# power_supply.net
KiCad netlist of a schematic drawn in Altium Designer
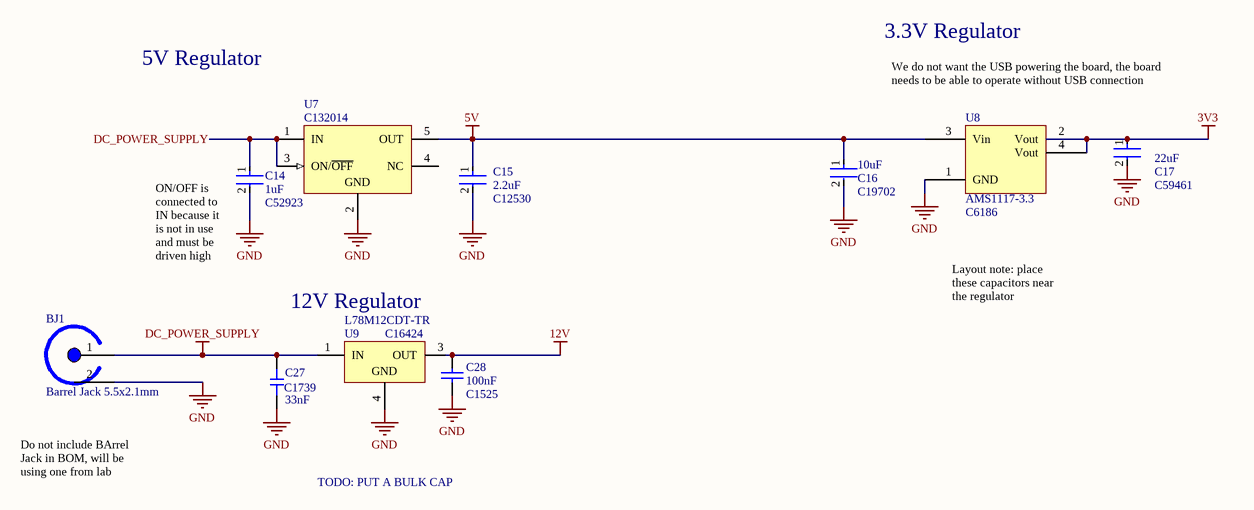
[diagram p0: power_supply.SchDoc]

(export (version "E")
  (design (tool "Eeschema 10.0.6"))
  (components
    (comp (ref "BJ1")
      (value "Barrel Jack 5.5x2.1mm")
      (footprint "Barrel Jack 2.1x5.5mm THT")
      (description "GCT DCJ200-10-A-K1-K")
      (fields (field (name "JLCPCB PART") "jlcpcb part no.") (field (name "SOURCE") "JCULibrary.SchLib"))
      (libsource (lib "James Cook University") (part "Barrel Jack 5.5x2.1mm"))
    )
    (comp (ref "C14")
      (value "CL05A105KA5NQNC")
      (footprint "FP-CL542-IPC_B")
      (description "Cap Ceramic 1uF 25V X5R ±10% SMD 0402 +85°C Paper T/R")
      (fields
        (field (name "TOLERANCE") "10%")
        (field (name "CAPACITANCE") "1uF")
        (field (name "JLCPCB PART") "C52923")
      )
      (libsource (lib "James Cook University") (part "b4654b650e69147ec39a6b967a45e02"))
    )
    (comp (ref "C15")
      (value "CL05A225MQ5NSNC")
      (footprint "FP-CL50-IPC_C")
      (description "Cap Ceramic 2.2uF 6.3V X5R ±20% SMD 0402 +85°C Paper T/R")
      (fields
        (field (name "CAPACITANCE") "2.2uF")
        (field (name "TOLERANCE") "20%")
        (field (name "JLCPCB PART") "C12530")
      )
      (libsource (lib "Altium Content Vault") (part "b4654b650e69147ec39a6b967a45e02"))
    )
    (comp (ref "C16")
      (value "CL10A106KP8NNNC")
      (footprint "FP-CL10-IPC_B")
      (description "Cap Ceramic 10uF 10V X5R ±10% Pad SMD 0603 +85°C T/R")
      (fields
        (field (name "JLCPCB PART") "C19702")
        (field (name "CAPACITANCE") "10uF")
        (field (name "TOLERANCE") "10%")
      )
      (libsource (lib "James Cook University") (part "b4654b650e69147ec39a6b967a45e02"))
    )
    (comp (ref "C17")
      (value "CL10A226MQ8NRNC")
      (footprint "FP-CL10-IPC_B")
      (description "Cap Ceramic 22uF 6.3V X5R ±20% Pad SMD 0603")
      (fields
        (field (name "JLCPCB PART") "C59461")
        (field (name "CAPACITANCE") "22uF")
        (field (name "TOLERANCE") "20%")
      )
      (libsource (lib "James Cook University") (part "b4654b650e69147ec39a6b967a45e02"))
    )
    (comp (ref "C27")
      (value "0805B333K500NT")
      (footprint "CAP-0805")
      (description "Capacitor, Ceramic (MLCC), 33nF, ±10%, 50V, X7R, ±10%, SMD 0805")
      (fields
        (field (name "CAPACITANCE") "33nF")
        (field (name "MANUFACTURER") "FH(Guangdong Fenghua Advanced Tech)")
        (field (name "TOLERANCE") "±10%")
        (field (name "JLCPCB PART") "C1739")
      )
      (libsource (lib "James Cook University") (part "GRM21BR61H106KE43L"))
    )
    (comp (ref "C28")
      (value "CL05B104KO5NNNC")
      (footprint "CAPC1050X55X23NL05T13")
      (description "Chip Capacitor, 100 nF, +/- 10%, 16 V, -55 to 125 degC, 0402 (1005 Metric), RoHS, Tape and Reel")
      (fields
        (field (name "MANUFACTURER") "Samsung Electro-Mechanics")
        (field (name "JLCPCB PART") "C1525")
        (field (name "CAPACITANCE") "100nF")
      )
      (libsource (lib "James Cook University") (part "CAP-NP-2"))
    )
    (comp (ref "U7")
      (value "LP2980AIM5-5.0/NOPB")
      (footprint "MF05A_M")
      (description "Micropower 50 mA Ultra Low-Dropout Regulator, 5-pin SOT-23, Pb-Free")
      (fields (field (name "MANUFACTURER") "National Semiconductor") (field (name "JLCPCB PART") "C132014"))
      (libsource (lib "Altium Content Vault") (part "PM-REG-LP2981-SOT5"))
    )
    (comp (ref "U8")
      (value "AMS1117-3.3")
      (footprint "SOT230P700X180-4N")
      (description "3.3V 1A LOW DROPOUT VOLTAGE REGULATOR SOT-223")
      (fields (field (name "JLCPCB PART") "C6186"))
      (libsource (lib "James Cook University") (part "AMS1117-3.3"))
    )
    (comp (ref "U9")
      (value "L78M12CDT-TR")
      (footprint "TO-252_L")
      (description "Positive Voltage Regulator, 12V, 3-Pin DPAK, Tape and Reel")
      (fields (field (name "JLCPCB PART") "C16424"))
      (libsource (lib "Altium Content Vault") (part "PM-REG-L4940-SOT3"))
    )
  )
  (nets
    (net (code "1") (name "3V3") (class "Default")
      (node (ref "C17") (pin "1") (pinfunction "1_1") (pintype "passive"))
      (node (ref "U8") (pin "2") (pinfunction "Vout_2") (pintype "power_in"))
      (node (ref "U8") (pin "4") (pinfunction "Vout_4") (pintype "power_in"))
    )
    (net (code "2") (name "5V") (class "Default")
      (node (ref "C15") (pin "1") (pinfunction "1_1") (pintype "passive"))
      (node (ref "C16") (pin "1") (pinfunction "1_1") (pintype "passive"))
      (node (ref "U7") (pin "5") (pinfunction "OUT_5") (pintype "power_in"))
      (node (ref "U8") (pin "3") (pinfunction "Vin_3") (pintype "power_in"))
    )
    (net (code "3") (name "12V") (class "Default")
      (node (ref "C28") (pin "2") (pinfunction "2_2") (pintype "passive"))
      (node (ref "U9") (pin "3") (pinfunction "OUT_3") (pintype "power_in"))
    )
    (net (code "4") (name "DC_POWER_SUPPLY") (class "Default")
      (node (ref "BJ1") (pin "1") (pinfunction "TIP_1") (pintype "power_in"))
      (node (ref "C14") (pin "1") (pinfunction "1_1") (pintype "passive"))
      (node (ref "C27") (pin "2") (pinfunction "2_2") (pintype "passive"))
      (node (ref "U7") (pin "1") (pinfunction "IN_1") (pintype "power_in"))
      (node (ref "U7") (pin "3") (pinfunction "ON/~{OFF}_3") (pintype "input"))
      (node (ref "U9") (pin "1") (pinfunction "IN_1") (pintype "power_in"))
    )
    (net (code "5") (name "GND") (class "Default")
      (node (ref "BJ1") (pin "2") (pinfunction "SLEEVE_2") (pintype "power_in"))
      (node (ref "C14") (pin "2") (pinfunction "2_2") (pintype "passive"))
      (node (ref "C15") (pin "2") (pinfunction "2_2") (pintype "passive"))
      (node (ref "C16") (pin "2") (pinfunction "2_2") (pintype "passive"))
      (node (ref "C17") (pin "2") (pinfunction "2_2") (pintype "passive"))
      (node (ref "C27") (pin "1") (pinfunction "1_1") (pintype "passive"))
      (node (ref "C28") (pin "1") (pinfunction "1_1") (pintype "passive"))
      (node (ref "U7") (pin "2") (pinfunction "GND_2") (pintype "power_in"))
      (node (ref "U8") (pin "1") (pinfunction "GND_1") (pintype "power_in"))
      (node (ref "U9") (pin "4") (pinfunction "GND_4") (pintype "power_in"))
    )
    (net (code "6") (name "unconnected-(U7-NC-Pad4)") (class "Default")
      (node (ref "U7") (pin "4") (pinfunction "NC_4") (pintype "passive"))
    )
  )
)
